# SP3232_module.net
KiCad netlist of a schematic drawn in Altium Designer
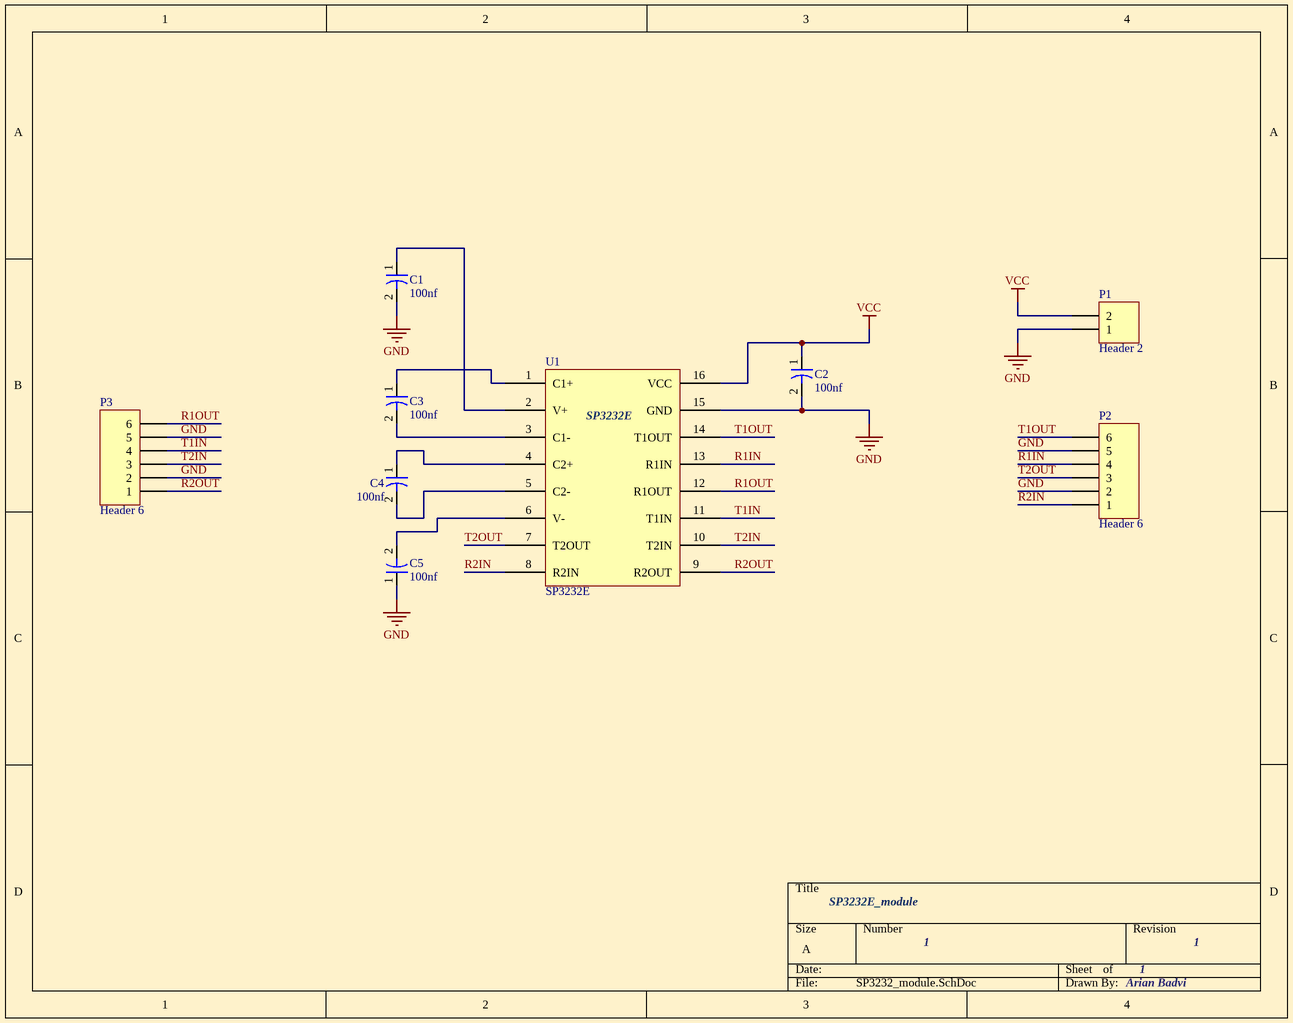
[diagram p0: SP3232_module.SchDoc]

(export (version "E")
  (design (tool "Eeschema 10.0.6"))
  (components
    (comp (ref "C1")
      (value "100nf")
      (footprint "CAP_SMD_A")
      (description "Capacitor, pol")
      (fields (field (name "PUBLISHER") "Altium Limited"))
      (libsource (lib "Miscellaneous Devices") (part "Cap2"))
    )
    (comp (ref "C2")
      (value "100nf")
      (footprint "CAP_SMD_A")
      (description "Capacitor, pol")
      (fields (field (name "PUBLISHER") "Altium Limited"))
      (libsource (lib "Miscellaneous Devices") (part "Cap2"))
    )
    (comp (ref "C3")
      (value "100nf")
      (footprint "CAP_SMD_A")
      (description "Capacitor, pol")
      (fields (field (name "PUBLISHER") "Altium Limited"))
      (libsource (lib "Miscellaneous Devices") (part "Cap2"))
    )
    (comp (ref "C4")
      (value "100nf")
      (footprint "CAP_SMD_A")
      (description "Capacitor, pol")
      (fields (field (name "PUBLISHER") "Altium Limited"))
      (libsource (lib "Miscellaneous Devices") (part "Cap2"))
    )
    (comp (ref "C5")
      (value "100nf")
      (footprint "CAP_SMD_A")
      (description "Capacitor, pol")
      (fields (field (name "PUBLISHER") "Altium Limited"))
      (libsource (lib "Miscellaneous Devices") (part "Cap2"))
    )
    (comp (ref "P1")
      (value "Header 2")
      (footprint "HDR_M_1X2")
      (description "Header, 2-Pin")
      (fields (field (name "PUBLISHER") "Altium Limited"))
      (libsource (lib "Miscellaneous Connectors") (part "Header 2"))
    )
    (comp (ref "P2")
      (value "Header 6")
      (footprint "HDR_M_1X6")
      (description "Header, 6-Pin")
      (fields (field (name "PUBLISHER") "Altium Limited"))
      (libsource (lib "Miscellaneous Connectors") (part "Header 6"))
    )
    (comp (ref "P3")
      (value "Header 6")
      (footprint "HDR_M_1X6")
      (description "Header, 6-Pin")
      (fields (field (name "PUBLISHER") "Altium Limited"))
      (libsource (lib "") (part "Header 6_1"))
    )
    (comp (ref "U1")
      (value "SP3232E")
      (footprint "so_16_w")
      (description "TTL to RS232 converter and vise versa")
      (libsource (lib "SP3232E") (part "SP3232E"))
    )
  )
  (nets
    (net (code "1") (name "/R1IN") (class "Default")
      (node (ref "P2") (pin "4") (pinfunction "4_4") (pintype "passive"))
      (node (ref "U1") (pin "13") (pinfunction "R1IN_13") (pintype "passive"))
    )
    (net (code "2") (name "/R1OUT") (class "Default")
      (node (ref "P3") (pin "6") (pinfunction "6_6") (pintype "passive"))
      (node (ref "U1") (pin "12") (pinfunction "R1OUT_12") (pintype "passive"))
    )
    (net (code "3") (name "/R2IN") (class "Default")
      (node (ref "P2") (pin "1") (pinfunction "1_1") (pintype "passive"))
      (node (ref "U1") (pin "8") (pinfunction "R2IN_8") (pintype "passive"))
    )
    (net (code "4") (name "/R2OUT") (class "Default")
      (node (ref "P3") (pin "1") (pinfunction "1_1") (pintype "passive"))
      (node (ref "U1") (pin "9") (pinfunction "R2OUT_9") (pintype "passive"))
    )
    (net (code "5") (name "/T1IN") (class "Default")
      (node (ref "P3") (pin "4") (pinfunction "4_4") (pintype "passive"))
      (node (ref "U1") (pin "11") (pinfunction "T1IN_11") (pintype "passive"))
    )
    (net (code "6") (name "/T1OUT") (class "Default")
      (node (ref "P2") (pin "6") (pinfunction "6_6") (pintype "passive"))
      (node (ref "U1") (pin "14") (pinfunction "T1OUT_14") (pintype "passive"))
    )
    (net (code "7") (name "/T2IN") (class "Default")
      (node (ref "P3") (pin "3") (pinfunction "3_3") (pintype "passive"))
      (node (ref "U1") (pin "10") (pinfunction "T2IN_10") (pintype "passive"))
    )
    (net (code "8") (name "/T2OUT") (class "Default")
      (node (ref "P2") (pin "3") (pinfunction "3_3") (pintype "passive"))
      (node (ref "U1") (pin "7") (pinfunction "T2OUT_7") (pintype "passive"))
    )
    (net (code "9") (name "GND") (class "Default")
      (node (ref "C1") (pin "2") (pinfunction "2_2") (pintype "passive"))
      (node (ref "C2") (pin "2") (pinfunction "2_2") (pintype "passive"))
      (node (ref "C5") (pin "1") (pinfunction "1_1") (pintype "passive"))
      (node (ref "P1") (pin "1") (pinfunction "1_1") (pintype "passive"))
      (node (ref "P2") (pin "2") (pinfunction "2_2") (pintype "passive"))
      (node (ref "P2") (pin "5") (pinfunction "5_5") (pintype "passive"))
      (node (ref "P3") (pin "2") (pinfunction "2_2") (pintype "passive"))
      (node (ref "P3") (pin "5") (pinfunction "5_5") (pintype "passive"))
      (node (ref "U1") (pin "15") (pinfunction "GND_15") (pintype "passive"))
    )
    (net (code "10") (name "Net-(U1-C1+)") (class "Default")
      (node (ref "C3") (pin "1") (pinfunction "1_1") (pintype "passive"))
      (node (ref "U1") (pin "1") (pinfunction "C1+_1") (pintype "passive"))
    )
    (net (code "11") (name "Net-(U1-C1-)") (class "Default")
      (node (ref "C3") (pin "2") (pinfunction "2_2") (pintype "passive"))
      (node (ref "U1") (pin "3") (pinfunction "C1-_3") (pintype "passive"))
    )
    (net (code "12") (name "Net-(U1-C2+)") (class "Default")
      (node (ref "C4") (pin "1") (pinfunction "1_1") (pintype "passive"))
      (node (ref "U1") (pin "4") (pinfunction "C2+_4") (pintype "passive"))
    )
    (net (code "13") (name "Net-(U1-C2-)") (class "Default")
      (node (ref "C4") (pin "2") (pinfunction "2_2") (pintype "passive"))
      (node (ref "U1") (pin "5") (pinfunction "C2-_5") (pintype "passive"))
    )
    (net (code "14") (name "Net-(U1-V+)") (class "Default")
      (node (ref "C1") (pin "1") (pinfunction "1_1") (pintype "passive"))
      (node (ref "U1") (pin "2") (pinfunction "V+_2") (pintype "passive"))
    )
    (net (code "15") (name "Net-(U1-V-)") (class "Default")
      (node (ref "C5") (pin "2") (pinfunction "2_2") (pintype "passive"))
      (node (ref "U1") (pin "6") (pinfunction "V-_6") (pintype "passive"))
    )
    (net (code "16") (name "VCC") (class "Default")
      (node (ref "C2") (pin "1") (pinfunction "1_1") (pintype "passive"))
      (node (ref "P1") (pin "2") (pinfunction "2_2") (pintype "passive"))
      (node (ref "U1") (pin "16") (pinfunction "VCC_16") (pintype "passive"))
    )
  )
)
